# ESP32_CONTROLLER_SHEET.net
KiCad netlist of a schematic drawn in Altium Designer
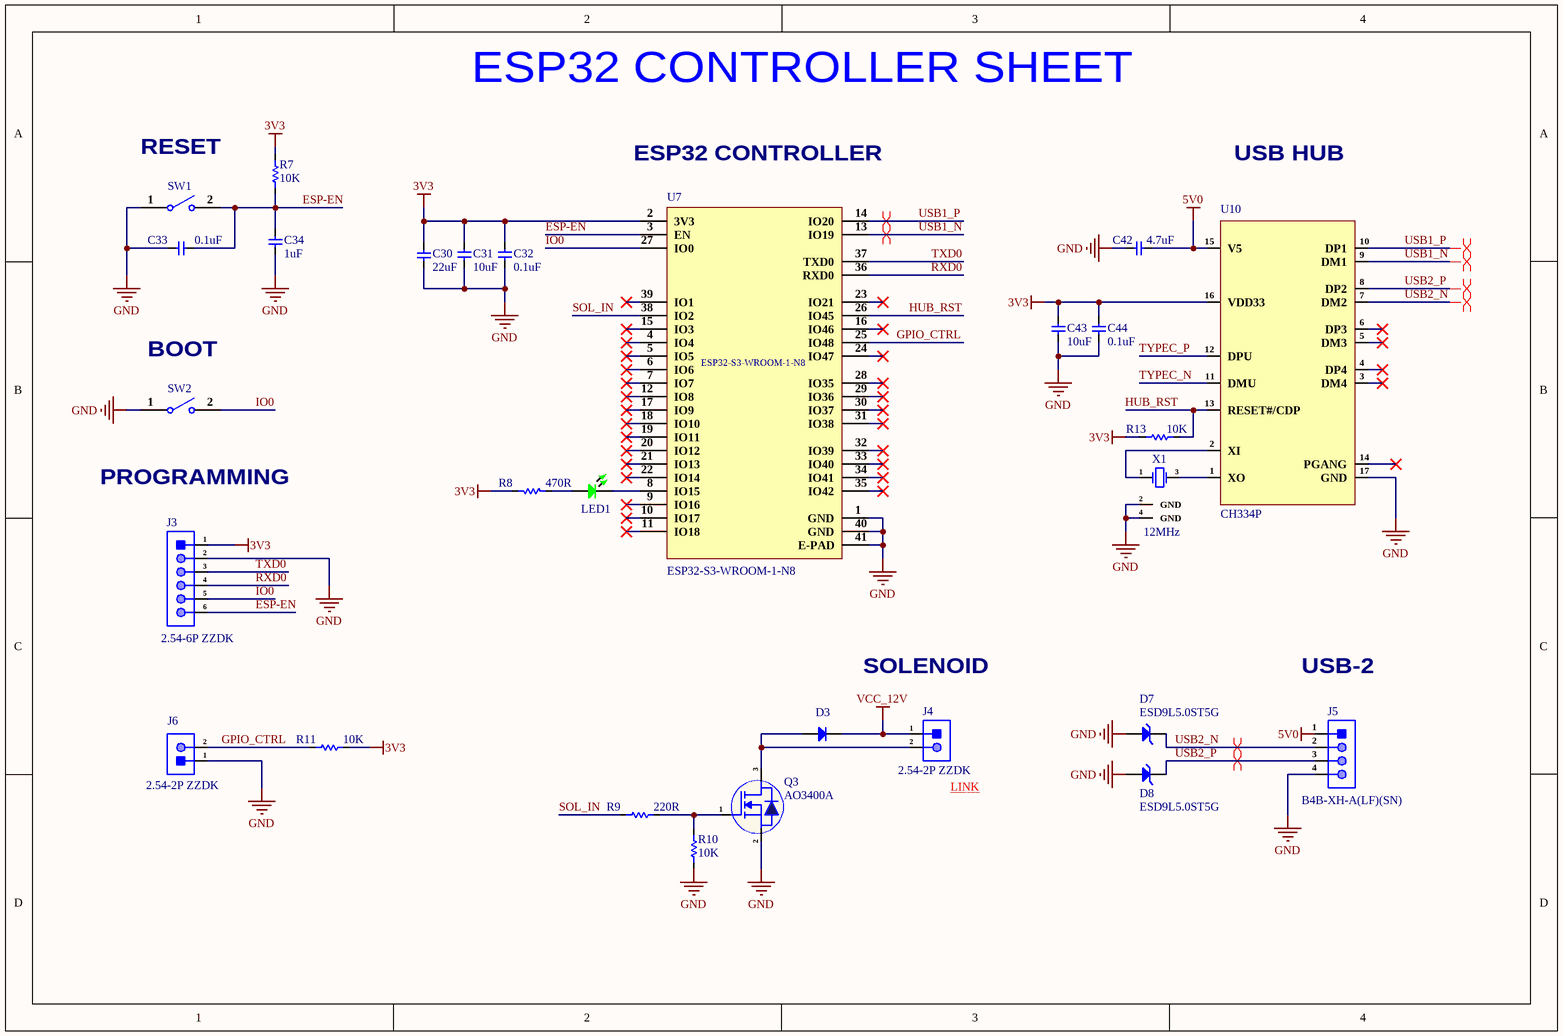
[diagram p0: ESP32_CONTROLLER_SHEET.SchDoc]

(export (version "E")
  (design (tool "Eeschema 10.0.6"))
  (components
    (comp (ref "C30")
      (value "22uF")
      (footprint "Cap-0603")
      (description "CAP CER 22UF 10V X5R 0603")
      (fields
        (field (name "MANUFACTURER") "Yageo")
        (field (name "MANUFACTURER PART NUMBER") "CC0603MRX5R6BB226")
      )
      (libsource (lib "eSpark Libraries") (part "CC0603MRX5R6BB226"))
    )
    (comp (ref "C31")
      (value "10uF")
      (footprint "Cap-0603")
      (description "CAP CER 10UF 16V X5R 0603")
      (fields
        (field (name "MANUFACTURER") "Yageo")
        (field (name "MANUFACTURER PART NUMBER") "CC0603KRX5R7BB106")
      )
      (libsource (lib "eSpark Libraries") (part "CC0603KRX5R7BB106"))
    )
    (comp (ref "C32")
      (value "0.1uF")
      (footprint "Cap-0402")
      (description "CAP CER 0.1UF 50V X7R 0402")
      (fields
        (field (name "MANUFACTURER") "Samsung")
        (field (name "MANUFACTURER PART NUMBER") "CL05B104KB54PNC")
      )
      (libsource (lib "eSpark Libraries") (part "CL05B104KB54PNC"))
    )
    (comp (ref "C33")
      (value "0.1uF")
      (footprint "Cap-0402")
      (description "CAP CER 0.1UF 50V X7R 0402")
      (fields
        (field (name "MANUFACTURER") "Samsung")
        (field (name "MANUFACTURER PART NUMBER") "CL05B104KB54PNC")
      )
      (libsource (lib "eSpark Libraries") (part "CL05B104KB54PNC"))
    )
    (comp (ref "C34")
      (value "1uF")
      (footprint "Cap-0402")
      (description "CAP CER 1UF 16V X5R 0402")
      (fields
        (field (name "MANUFACTURER") "Yageo")
        (field (name "MANUFACTURER PART NUMBER") "CC0402KRX5R7BB105")
      )
      (libsource (lib "eSpark Libraries") (part "CC0402KRX5R7BB105"))
    )
    (comp (ref "C42")
      (value "4.7uF")
      (footprint "Cap-0402")
      (description "CAP CER 4.7UF 16V X5R 0402")
      (fields
        (field (name "MANUFACTURER") "Samsung")
        (field (name "MANUFACTURER PART NUMBER") "CL05A475MO5NUNC")
      )
      (libsource (lib "eSpark Libraries") (part "CL05A475MO5NUNC"))
    )
    (comp (ref "C43")
      (value "10uF")
      (footprint "Cap-0603")
      (description "CAP CER 10UF 16V X5R 0603")
      (fields
        (field (name "MANUFACTURER") "Yageo")
        (field (name "MANUFACTURER PART NUMBER") "CC0603KRX5R7BB106")
      )
      (libsource (lib "eSpark Libraries") (part "CC0603KRX5R7BB106"))
    )
    (comp (ref "C44")
      (value "0.1uF")
      (footprint "Cap-0402")
      (description "CAP CER 0.1UF 50V X7R 0402")
      (fields
        (field (name "MANUFACTURER") "Samsung")
        (field (name "MANUFACTURER PART NUMBER") "CL05B104KB54PNC")
      )
      (libsource (lib "eSpark Libraries") (part "CL05B104KB54PNC"))
    )
    (comp (ref "D3")
      (value "1N4148W")
      (footprint "SOD-123")
      (description "100V 400mW Single 1.25V@150mA 8ns 300mA SOD-123 Switching Diode ROHS")
      (fields (field (name "MANUFACTURER") "JSMSEMI") (field (name "LCSC PART NUMBER") "C917030"))
      (libsource (lib "eSpark Libraries") (part "1N4148W"))
    )
    (comp (ref "D7")
      (value "ESD9L5.0ST5G")
      (footprint "SOD-923.")
      (fields (field (name "MANUFACTURER") "ON Semiconductor") (field (name "LCSC PART NUMBER") "C82326"))
      (libsource (lib "eSpark Libraries") (part "ESD9L5.0ST5G"))
    )
    (comp (ref "D8")
      (value "ESD9L5.0ST5G")
      (footprint "SOD-923.")
      (description "TVS DIODE 5V 9.8V SOD923")
      (fields (field (name "MANUFACTURER") "ON Semiconductor") (field (name "LCSC PART NUMBER") "C82326"))
      (libsource (lib "eSpark Libraries") (part "ESD9L5.0ST5G"))
    )
    (comp (ref "J3")
      (value "2.54-6P ZZDK")
      (footprint "2.54-6P ZZDK")
      (description "CONN HEADER TH 6POS 2.5mm")
      (fields (field (name "MANUFACTURER") "SHOU HAN") (field (name "LCSC PART NUMBER") "C18185653"))
      (libsource (lib "DOCK_ESP32_v1.0") (part "2.54-6P ZZDK"))
    )
    (comp (ref "J4")
      (value "2.54-2P ZZDK")
      (footprint "2.54-2P ZZDK")
      (fields (field (name "MANUFACTURER") "SHOU HAN") (field (name "LCSC PART NUMBER") "C18185649"))
      (libsource (lib "eSpark Libraries") (part "2.54-2P ZZDK"))
    )
    (comp (ref "J5")
      (value "B4B-XH-A(LF)(SN)")
      (footprint "B4B-XH-A(LF)(SN).")
      (description "CONN HEADER VERT 4POS 2.5MM")
      (fields (field (name "MANUFACTURER") "JST") (field (name "LCSC PART NUMBER") "C144395"))
      (libsource (lib "eSpark Libraries") (part "B4B-XH-A(LF)(SN)"))
    )
    (comp (ref "J6")
      (value "2.54-2P ZZDK")
      (footprint "2.54-2P ZZDK")
      (fields (field (name "MANUFACTURER") "SHOU HAN") (field (name "LCSC PART NUMBER") "C18185649"))
      (libsource (lib "") (part "2.54-2P ZZDK_1"))
    )
    (comp (ref "LED1")
      (value "Emerald")
      (footprint "LED-0603")
      (description "Emerald 0603 Light Emitting Diodes (LED) ROHS")
      (fields
        (field (name "MANUFACTURER") "Foshan NationStar Optoelectronics")
        (field (name "MANUFACTURER PART NUMBER") "NCD0603G2")
      )
      (libsource (lib "eSpark Libraries") (part "NCD0603G2"))
    )
    (comp (ref "Q3")
      (value "AO3400A")
      (footprint "sot-23")
      (description "30V 5.8A 32mΩ@10V,5.8A 1.4W 1.4V@250uA N Channel SOT-23 MOSFETs ROHS")
      (fields (field (name "MANUFACTURER") "BORN") (field (name "LCSC PART NUMBER") "C344010"))
      (libsource (lib "eSpark Libraries") (part "AO3400A"))
    )
    (comp (ref "R7")
      (value "10K")
      (footprint "Res-0402")
      (description "RES 10K OHM 1% 1/16W 0402")
      (fields
        (field (name "MANUFACTURER") "Yageo")
        (field (name "MANUFACTURER PART NUMBER") "RC0402FR-0710KL")
      )
      (libsource (lib "eSpark Libraries") (part "RC0402FR-0710KL"))
    )
    (comp (ref "R8")
      (value "470R")
      (footprint "Res-0402")
      (description "RES 470 OHM 1% 1/16W 0402")
      (fields
        (field (name "MANUFACTURER") "Yageo")
        (field (name "MANUFACTURER PART NUMBER") "RC0402FR-07470RL")
      )
      (libsource (lib "eSpark Libraries") (part "RC0402FR-07470RL"))
    )
    (comp (ref "R9")
      (value "220R")
      (footprint "Res-0402")
      (description "RES 220 OHM 1% 1/16W 0402")
      (fields (field (name "LCSC PART NUMBER") "C112291") (field (name "MANUFACTURER") "Yageo"))
      (libsource (lib "eSpark Libraries") (part "RC0402FR-07220RL"))
    )
    (comp (ref "R10")
      (value "10K")
      (footprint "Res-0402")
      (description "RES 10K OHM 1% 1/16W 0402")
      (fields
        (field (name "MANUFACTURER") "Yageo")
        (field (name "MANUFACTURER PART NUMBER") "RC0402FR-0710KL")
      )
      (libsource (lib "eSpark Libraries") (part "RC0402FR-0710KL"))
    )
    (comp (ref "R11")
      (value "10K")
      (footprint "Res-0402")
      (description "RES 10K OHM 1% 1/16W 0402")
      (fields
        (field (name "MANUFACTURER") "Yageo")
        (field (name "MANUFACTURER PART NUMBER") "RC0402FR-0710KL")
      )
      (libsource (lib "eSpark Libraries") (part "RC0402FR-0710KL"))
    )
    (comp (ref "R13")
      (value "10K")
      (footprint "Res-0402")
      (description "RES 10K OHM 1% 1/16W 0402")
      (fields
        (field (name "MANUFACTURER") "Yageo")
        (field (name "MANUFACTURER PART NUMBER") "RC0402FR-0710KL")
      )
      (libsource (lib "eSpark Libraries") (part "RC0402FR-0710KL"))
    )
    (comp (ref "SW1")
      (value "GT-TC032A-H015-L1")
      (footprint "GT-TC032A-H015-L1")
      (fields (field (name "MANUFACTURER") "G-Switch") (field (name "LCSC PART NUMBER") "C843684"))
      (libsource (lib "eSpark Libraries") (part "GT-TC032A-H015-L1"))
    )
    (comp (ref "SW2")
      (value "GT-TC032A-H015-L1")
      (footprint "GT-TC032A-H015-L1")
      (fields (field (name "MANUFACTURER") "G-Switch") (field (name "LCSC PART NUMBER") "C843684"))
      (libsource (lib "eSpark Libraries") (part "GT-TC032A-H015-L1"))
    )
    (comp (ref "U7")
      (value "ESP32-S3-WROOM-1-N8")
      (footprint "41-SMD Module")
      (description "ESP32-S3 chip 2.4GHz SMD,18x25.5mm WiFi Modules ROHS")
      (fields (field (name "MANUFACTURER") "Expressif System") (field (name "LCSC PART NUMBER") "C2913198"))
      (libsource (lib "eSpark Libraries") (part "ESP32-S3-WROOM-1-N8"))
    )
    (comp (ref "U10")
      (value "CH334P")
      (footprint "QFN-16")
      (description "480Mbps Hub USB 2.0 QFN-16(3x3) Interface Controllers RoHS")
      (fields (field (name "LCSC PART NUMBER") "C5373042"))
      (libsource (lib "DOCK_ESP32_v1.0") (part "CH334P"))
    )
    (comp (ref "X1")
      (value "12MHz")
      (footprint "SMD2520-4P")
      (description "12MHz 18pF ±10ppm SMD2520-4P Crystals ROHS")
      (fields (field (name "MANUFACTURER") "JYJE") (field (name "MANUFACTURER PART NUMBER") "2TJ412000XYGBC"))
      (libsource (lib "eSpark Libraries") (part "2TJ412000XYGBC"))
    )
  )
  (nets
    (net (code "1") (name "/ESP-EN") (class "Default")
      (node (ref "C33") (pin "1") (pinfunction "1_1") (pintype "passive"))
      (node (ref "C34") (pin "2") (pinfunction "2_2") (pintype "passive"))
      (node (ref "J3") (pin "6") (pinfunction "6_6") (pintype "passive"))
      (node (ref "R7") (pin "1") (pinfunction "1_1") (pintype "passive"))
      (node (ref "SW1") (pin "2") (pinfunction "2_2") (pintype "passive"))
      (node (ref "U7") (pin "3") (pinfunction "EN_3") (pintype "passive"))
    )
    (net (code "2") (name "/GPIO_CTRL") (class "Default")
      (node (ref "J6") (pin "2") (pinfunction "2_2") (pintype "passive"))
      (node (ref "R11") (pin "1") (pinfunction "1_1") (pintype "passive"))
      (node (ref "U7") (pin "25") (pinfunction "IO48_25") (pintype "passive"))
    )
    (net (code "3") (name "/HUB_RST") (class "Default")
      (node (ref "R13") (pin "1") (pinfunction "1_1") (pintype "passive"))
      (node (ref "U10") (pin "13") (pinfunction "RESET#/CDP_13") (pintype "passive"))
      (node (ref "U7") (pin "26") (pinfunction "IO45_26") (pintype "passive"))
    )
    (net (code "4") (name "/IO0") (class "Default")
      (node (ref "J3") (pin "5") (pinfunction "5_5") (pintype "passive"))
      (node (ref "SW2") (pin "2") (pinfunction "2_2") (pintype "passive"))
      (node (ref "U7") (pin "27") (pinfunction "IO0_27") (pintype "passive"))
    )
    (net (code "5") (name "/RXD0") (class "Default")
      (node (ref "J3") (pin "4") (pinfunction "4_4") (pintype "passive"))
      (node (ref "U7") (pin "36") (pinfunction "RXD0_36") (pintype "passive"))
    )
    (net (code "6") (name "/SOL_IN") (class "Default")
      (node (ref "R9") (pin "1") (pinfunction "1_1") (pintype "passive"))
      (node (ref "U7") (pin "38") (pinfunction "IO2_38") (pintype "passive"))
    )
    (net (code "7") (name "/TXD0") (class "Default")
      (node (ref "J3") (pin "3") (pinfunction "3_3") (pintype "passive"))
      (node (ref "U7") (pin "37") (pinfunction "TXD0_37") (pintype "passive"))
    )
    (net (code "8") (name "/TYPEC_N") (class "Default")
      (node (ref "U10") (pin "11") (pinfunction "DMU_11") (pintype "passive"))
    )
    (net (code "9") (name "/TYPEC_P") (class "Default")
      (node (ref "U10") (pin "12") (pinfunction "DPU_12") (pintype "passive"))
    )
    (net (code "10") (name "/USB1_N") (class "Default")
      (node (ref "U10") (pin "9") (pinfunction "DM1_9") (pintype "passive"))
      (node (ref "U7") (pin "13") (pinfunction "IO19_13") (pintype "passive"))
    )
    (net (code "11") (name "/USB1_P") (class "Default")
      (node (ref "U10") (pin "10") (pinfunction "DP1_10") (pintype "passive"))
      (node (ref "U7") (pin "14") (pinfunction "IO20_14") (pintype "passive"))
    )
    (net (code "12") (name "/USB2_N") (class "Default")
      (node (ref "D7") (pin "1") (pinfunction "K_1") (pintype "passive"))
      (node (ref "J5") (pin "2") (pinfunction "2_2") (pintype "passive"))
      (node (ref "U10") (pin "7") (pinfunction "DM2_7") (pintype "passive"))
    )
    (net (code "13") (name "/USB2_P") (class "Default")
      (node (ref "D8") (pin "1") (pinfunction "K_1") (pintype "passive"))
      (node (ref "J5") (pin "3") (pinfunction "3_3") (pintype "passive"))
      (node (ref "U10") (pin "8") (pinfunction "DP2_8") (pintype "passive"))
    )
    (net (code "14") (name "3V3") (class "Default")
      (node (ref "C30") (pin "2") (pinfunction "2_2") (pintype "passive"))
      (node (ref "C31") (pin "1") (pinfunction "1_1") (pintype "passive"))
      (node (ref "C32") (pin "1") (pinfunction "1_1") (pintype "passive"))
      (node (ref "C43") (pin "1") (pinfunction "1_1") (pintype "passive"))
      (node (ref "C44") (pin "1") (pinfunction "1_1") (pintype "passive"))
      (node (ref "J3") (pin "1") (pinfunction "1_1") (pintype "passive"))
      (node (ref "R11") (pin "2") (pinfunction "2_2") (pintype "passive"))
      (node (ref "R13") (pin "2") (pinfunction "2_2") (pintype "passive"))
      (node (ref "R7") (pin "2") (pinfunction "2_2") (pintype "passive"))
      (node (ref "R8") (pin "2") (pinfunction "2_2") (pintype "passive"))
      (node (ref "U10") (pin "16") (pinfunction "VDD33_16") (pintype "passive"))
      (node (ref "U7") (pin "2") (pinfunction "3V3_2") (pintype "passive"))
    )
    (net (code "15") (name "5V0") (class "Default")
      (node (ref "C42") (pin "2") (pinfunction "2_2") (pintype "passive"))
      (node (ref "J5") (pin "1") (pinfunction "1_1") (pintype "passive"))
      (node (ref "U10") (pin "15") (pinfunction "V5_15") (pintype "passive"))
    )
    (net (code "16") (name "GND") (class "Default")
      (node (ref "C30") (pin "1") (pinfunction "1_1") (pintype "passive"))
      (node (ref "C31") (pin "2") (pinfunction "2_2") (pintype "passive"))
      (node (ref "C32") (pin "2") (pinfunction "2_2") (pintype "passive"))
      (node (ref "C33") (pin "2") (pinfunction "2_2") (pintype "passive"))
      (node (ref "C34") (pin "1") (pinfunction "1_1") (pintype "passive"))
      (node (ref "C42") (pin "1") (pinfunction "1_1") (pintype "passive"))
      (node (ref "C43") (pin "2") (pinfunction "2_2") (pintype "passive"))
      (node (ref "C44") (pin "2") (pinfunction "2_2") (pintype "passive"))
      (node (ref "D7") (pin "2") (pinfunction "A_2") (pintype "passive"))
      (node (ref "D8") (pin "2") (pinfunction "A_2") (pintype "passive"))
      (node (ref "J3") (pin "2") (pinfunction "2_2") (pintype "passive"))
      (node (ref "J5") (pin "4") (pinfunction "4_4") (pintype "passive"))
      (node (ref "J6") (pin "1") (pinfunction "1_1") (pintype "passive"))
      (node (ref "Q3") (pin "2") (pinfunction "S_2") (pintype "passive"))
      (node (ref "R10") (pin "1") (pinfunction "1_1") (pintype "passive"))
      (node (ref "SW1") (pin "1") (pinfunction "1_1") (pintype "passive"))
      (node (ref "SW2") (pin "1") (pinfunction "1_1") (pintype "passive"))
      (node (ref "U10") (pin "17") (pinfunction "GND_17") (pintype "passive"))
      (node (ref "U7") (pin "1") (pinfunction "GND_1") (pintype "passive"))
      (node (ref "U7") (pin "40") (pinfunction "GND_40") (pintype "passive"))
      (node (ref "U7") (pin "41") (pinfunction "E-PAD_41") (pintype "passive"))
      (node (ref "X1") (pin "2") (pinfunction "GND_2") (pintype "passive"))
      (node (ref "X1") (pin "4") (pinfunction "GND_4") (pintype "passive"))
    )
    (net (code "17") (name "Net-(D3-A)") (class "Default")
      (node (ref "D3") (pin "1") (pinfunction "A_1") (pintype "passive"))
      (node (ref "J4") (pin "2") (pinfunction "2_2") (pintype "passive"))
      (node (ref "Q3") (pin "3") (pinfunction "D_3") (pintype "passive"))
    )
    (net (code "18") (name "Net-(LED1-Pad1)") (class "Default")
      (node (ref "LED1") (pin "1") (pinfunction "1_1") (pintype "passive"))
      (node (ref "R8") (pin "1") (pinfunction "1_1") (pintype "passive"))
    )
    (net (code "19") (name "Net-(Q3-G)") (class "Default")
      (node (ref "Q3") (pin "1") (pinfunction "G_1") (pintype "passive"))
      (node (ref "R10") (pin "2") (pinfunction "2_2") (pintype "passive"))
      (node (ref "R9") (pin "2") (pinfunction "2_2") (pintype "passive"))
    )
    (net (code "20") (name "Net-(U7-IO15)") (class "Default")
      (node (ref "LED1") (pin "2") (pinfunction "2_2") (pintype "passive"))
      (node (ref "U7") (pin "8") (pinfunction "IO15_8") (pintype "passive"))
    )
    (net (code "21") (name "Net-(U10-XI)") (class "Default")
      (node (ref "U10") (pin "2") (pinfunction "XI_2") (pintype "passive"))
      (node (ref "X1") (pin "1") (pinfunction "OSC1_1") (pintype "passive"))
    )
    (net (code "22") (name "Net-(U10-XO)") (class "Default")
      (node (ref "U10") (pin "1") (pinfunction "XO_1") (pintype "passive"))
      (node (ref "X1") (pin "3") (pinfunction "OSC2_3") (pintype "passive"))
    )
    (net (code "23") (name "VCC_12V") (class "Default")
      (node (ref "D3") (pin "2") (pinfunction "K_2") (pintype "passive"))
      (node (ref "J4") (pin "1") (pinfunction "1_1") (pintype "passive"))
    )
    (net (code "24") (name "unconnected-(U7-IO1-Pad39)") (class "Default")
      (node (ref "U7") (pin "39") (pinfunction "IO1_39") (pintype "passive+no_connect"))
    )
    (net (code "25") (name "unconnected-(U7-IO3-Pad15)") (class "Default")
      (node (ref "U7") (pin "15") (pinfunction "IO3_15") (pintype "passive+no_connect"))
    )
    (net (code "26") (name "unconnected-(U7-IO4-Pad4)") (class "Default")
      (node (ref "U7") (pin "4") (pinfunction "IO4_4") (pintype "passive+no_connect"))
    )
    (net (code "27") (name "unconnected-(U7-IO5-Pad5)") (class "Default")
      (node (ref "U7") (pin "5") (pinfunction "IO5_5") (pintype "passive+no_connect"))
    )
    (net (code "28") (name "unconnected-(U7-IO6-Pad6)") (class "Default")
      (node (ref "U7") (pin "6") (pinfunction "IO6_6") (pintype "passive+no_connect"))
    )
    (net (code "29") (name "unconnected-(U7-IO7-Pad7)") (class "Default")
      (node (ref "U7") (pin "7") (pinfunction "IO7_7") (pintype "passive+no_connect"))
    )
    (net (code "30") (name "unconnected-(U7-IO8-Pad12)") (class "Default")
      (node (ref "U7") (pin "12") (pinfunction "IO8_12") (pintype "passive+no_connect"))
    )
    (net (code "31") (name "unconnected-(U7-IO9-Pad17)") (class "Default")
      (node (ref "U7") (pin "17") (pinfunction "IO9_17") (pintype "passive+no_connect"))
    )
    (net (code "32") (name "unconnected-(U7-IO10-Pad18)") (class "Default")
      (node (ref "U7") (pin "18") (pinfunction "IO10_18") (pintype "passive+no_connect"))
    )
    (net (code "33") (name "unconnected-(U7-IO11-Pad19)") (class "Default")
      (node (ref "U7") (pin "19") (pinfunction "IO11_19") (pintype "passive+no_connect"))
    )
    (net (code "34") (name "unconnected-(U7-IO12-Pad20)") (class "Default")
      (node (ref "U7") (pin "20") (pinfunction "IO12_20") (pintype "passive+no_connect"))
    )
    (net (code "35") (name "unconnected-(U7-IO13-Pad21)") (class "Default")
      (node (ref "U7") (pin "21") (pinfunction "IO13_21") (pintype "passive+no_connect"))
    )
    (net (code "36") (name "unconnected-(U7-IO14-Pad22)") (class "Default")
      (node (ref "U7") (pin "22") (pinfunction "IO14_22") (pintype "passive+no_connect"))
    )
    (net (code "37") (name "unconnected-(U7-IO16-Pad9)") (class "Default")
      (node (ref "U7") (pin "9") (pinfunction "IO16_9") (pintype "passive+no_connect"))
    )
    (net (code "38") (name "unconnected-(U7-IO17-Pad10)") (class "Default")
      (node (ref "U7") (pin "10") (pinfunction "IO17_10") (pintype "passive+no_connect"))
    )
    (net (code "39") (name "unconnected-(U7-IO18-Pad11)") (class "Default")
      (node (ref "U7") (pin "11") (pinfunction "IO18_11") (pintype "passive+no_connect"))
    )
    (net (code "40") (name "unconnected-(U7-IO21-Pad23)") (class "Default")
      (node (ref "U7") (pin "23") (pinfunction "IO21_23") (pintype "passive+no_connect"))
    )
    (net (code "41") (name "unconnected-(U7-IO35-Pad28)") (class "Default")
      (node (ref "U7") (pin "28") (pinfunction "IO35_28") (pintype "passive+no_connect"))
    )
    (net (code "42") (name "unconnected-(U7-IO36-Pad29)") (class "Default")
      (node (ref "U7") (pin "29") (pinfunction "IO36_29") (pintype "passive+no_connect"))
    )
    (net (code "43") (name "unconnected-(U7-IO37-Pad30)") (class "Default")
      (node (ref "U7") (pin "30") (pinfunction "IO37_30") (pintype "passive+no_connect"))
    )
    (net (code "44") (name "unconnected-(U7-IO38-Pad31)") (class "Default")
      (node (ref "U7") (pin "31") (pinfunction "IO38_31") (pintype "passive+no_connect"))
    )
    (net (code "45") (name "unconnected-(U7-IO39-Pad32)") (class "Default")
      (node (ref "U7") (pin "32") (pinfunction "IO39_32") (pintype "passive+no_connect"))
    )
    (net (code "46") (name "unconnected-(U7-IO40-Pad33)") (class "Default")
      (node (ref "U7") (pin "33") (pinfunction "IO40_33") (pintype "passive+no_connect"))
    )
    (net (code "47") (name "unconnected-(U7-IO41-Pad34)") (class "Default")
      (node (ref "U7") (pin "34") (pinfunction "IO41_34") (pintype "passive+no_connect"))
    )
    (net (code "48") (name "unconnected-(U7-IO42-Pad35)") (class "Default")
      (node (ref "U7") (pin "35") (pinfunction "IO42_35") (pintype "passive+no_connect"))
    )
    (net (code "49") (name "unconnected-(U7-IO46-Pad16)") (class "Default")
      (node (ref "U7") (pin "16") (pinfunction "IO46_16") (pintype "passive+no_connect"))
    )
    (net (code "50") (name "unconnected-(U7-IO47-Pad24)") (class "Default")
      (node (ref "U7") (pin "24") (pinfunction "IO47_24") (pintype "passive+no_connect"))
    )
    (net (code "51") (name "unconnected-(U10-DM3-Pad5)") (class "Default")
      (node (ref "U10") (pin "5") (pinfunction "DM3_5") (pintype "passive+no_connect"))
    )
    (net (code "52") (name "unconnected-(U10-DM4-Pad3)") (class "Default")
      (node (ref "U10") (pin "3") (pinfunction "DM4_3") (pintype "passive+no_connect"))
    )
    (net (code "53") (name "unconnected-(U10-DP3-Pad6)") (class "Default")
      (node (ref "U10") (pin "6") (pinfunction "DP3_6") (pintype "passive+no_connect"))
    )
    (net (code "54") (name "unconnected-(U10-DP4-Pad4)") (class "Default")
      (node (ref "U10") (pin "4") (pinfunction "DP4_4") (pintype "passive+no_connect"))
    )
    (net (code "55") (name "unconnected-(U10-PGANG-Pad14)") (class "Default")
      (node (ref "U10") (pin "14") (pinfunction "PGANG_14") (pintype "passive+no_connect"))
    )
  )
)
